# Sheet4.net
KiCad netlist of a schematic drawn in Altium Designer
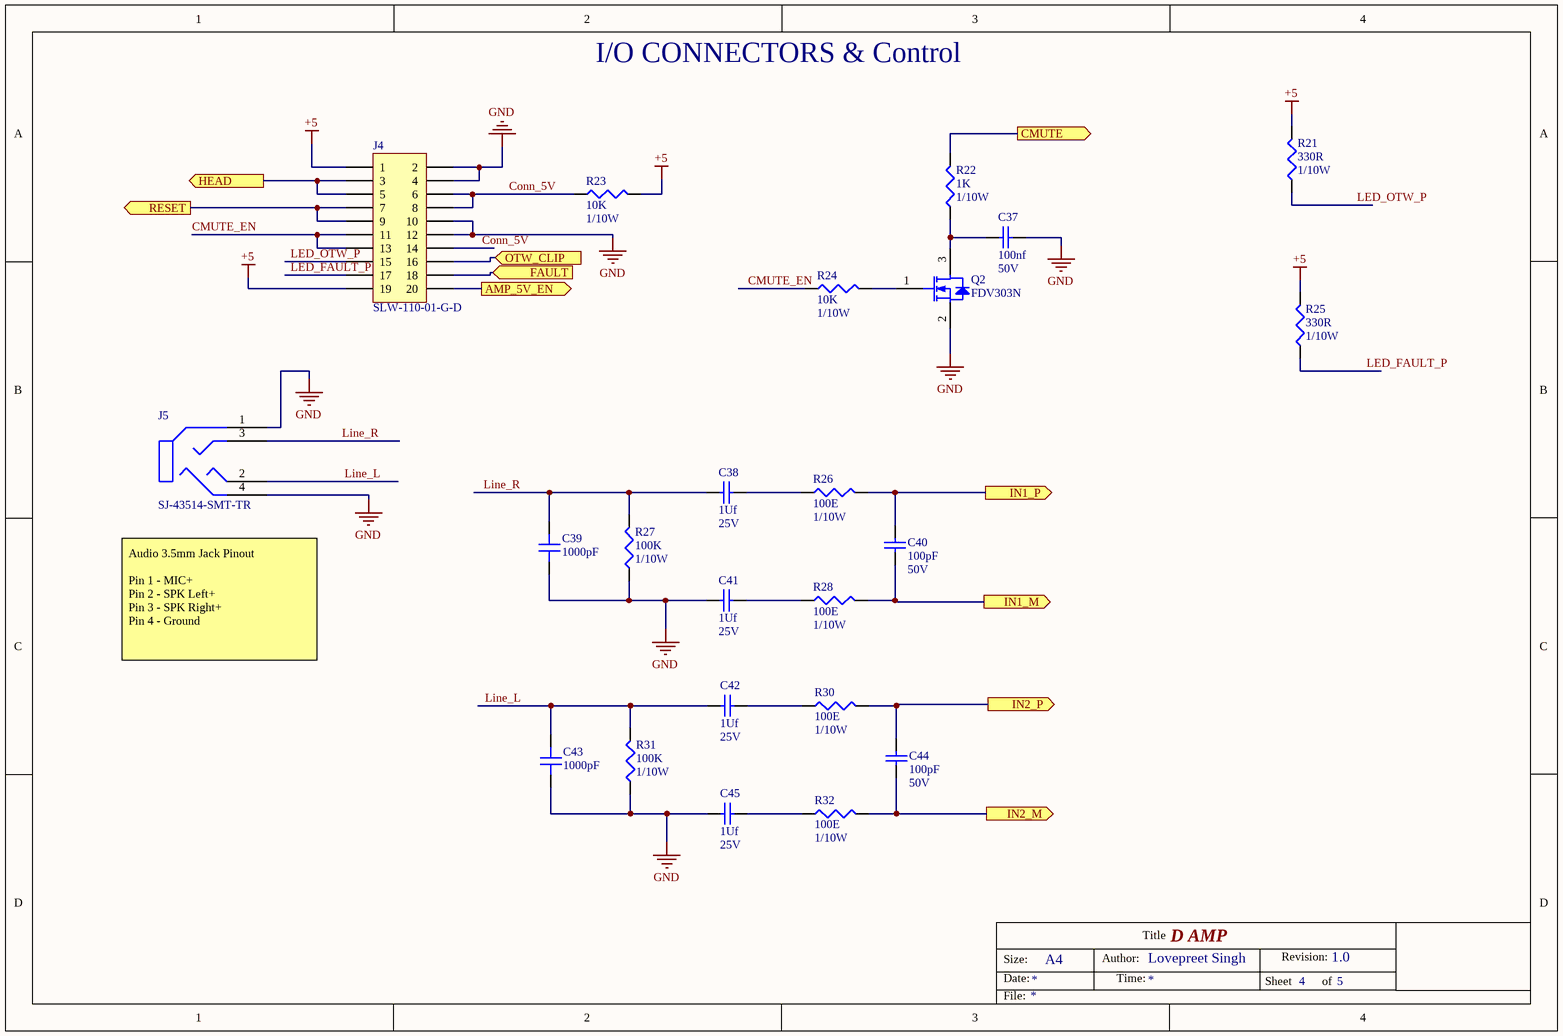
[diagram p0: Sheet4.SchDoc]

(export (version "E")
  (design (tool "Eeschema 10.0.6"))
  (components
    (comp (ref "C37")
      (value "100nf")
      (footprint "C0603")
      (description "CAP CER 100NF 10% 50V X7R 0603")
      (fields (field (name "VRATING") "50V"))
      (libsource (lib "Database_Libs1") (part "CAP_NPOL"))
    )
    (comp (ref "C38")
      (value "1Uf")
      (footprint "C0603")
      (description "CAP MLCC SMD 25V 1uF 10% X7R 0603")
      (fields (field (name "VRATING") "25V"))
      (libsource (lib "Database_Libs1") (part "CAP_NPOL"))
    )
    (comp (ref "C39")
      (value "1000pF")
      (footprint "CAP 0603_1608")
      (description "CAP CER 0603 1NF 16V X7R 10%")
      (fields (field (name "PART NUMBER") "C0603C102K4RECAUTO") (field (name "MANUFACTURER") "KEMET"))
      (libsource (lib "Celestial Altium Library - altium_library") (part "Capacitor"))
    )
    (comp (ref "C40")
      (value "100pF")
      (footprint "C0603")
      (description "CAP 100PF 5% 50V 0603")
      (fields (field (name "VRATING") "50V"))
      (libsource (lib "Database_Libs1") (part "CAP_NPOL"))
    )
    (comp (ref "C41")
      (value "1Uf")
      (footprint "C0603")
      (description "CAP MLCC SMD 25V 1uF 10% X7R 0603")
      (fields (field (name "VRATING") "25V"))
      (libsource (lib "Database_Libs1") (part "CAP_NPOL"))
    )
    (comp (ref "C42")
      (value "1Uf")
      (footprint "C0603")
      (description "CAP MLCC SMD 25V 1uF 10% X7R 0603")
      (fields (field (name "VRATING") "25V"))
      (libsource (lib "Database_Libs1") (part "CAP_NPOL"))
    )
    (comp (ref "C43")
      (value "1000pF")
      (footprint "CAP 0603_1608")
      (description "CAP CER 0603 1NF 16V X7R 10%")
      (fields (field (name "PART NUMBER") "C0603C102K4RECAUTO") (field (name "MANUFACTURER") "KEMET"))
      (libsource (lib "Celestial Altium Library - altium_library") (part "Capacitor"))
    )
    (comp (ref "C44")
      (value "100pF")
      (footprint "C0603")
      (description "CAP 100PF 5% 50V 0603")
      (fields (field (name "VRATING") "50V"))
      (libsource (lib "Database_Libs1") (part "CAP_NPOL"))
    )
    (comp (ref "C45")
      (value "1Uf")
      (footprint "C0603")
      (description "CAP MLCC SMD 25V 1uF 10% X7R 0603")
      (fields (field (name "VRATING") "25V"))
      (libsource (lib "Database_Libs1") (part "CAP_NPOL"))
    )
    (comp (ref "J4")
      (value "SLW-110-01-G-D")
      (footprint "HDR2X10")
      (description "CONN HSG 20PIN 2.54MM STR DUALROW")
      (libsource (lib "Database_Libs1") (part "Header 10X2"))
    )
    (comp (ref "J5")
      (value "SJ-43514-SMT-TR")
      (footprint "CUI SJ-43514-SMT-TR")
      (description "CONN JACK 4COND 3.5MM SMD R/A")
      (fields (field (name "MANUFACTURER") "CUI Devices"))
      (libsource (lib "Celestial Altium Library - altium_library") (part "CUI SJ-43514"))
    )
    (comp (ref "Q2")
      (value "FDV303N")
      (footprint "SOT23_123")
      (description "TRANS N-CH MOSFET 25V 0.68A SOT23")
      (libsource (lib "Database_Libs1") (part "FDV303N"))
    )
    (comp (ref "R21")
      (value "330R")
      (footprint "R0603")
      (description "RES  SMD 330R 5% 1/10W 0603")
      (fields (field (name "PRATING") "1/10W"))
      (libsource (lib "Database_Libs1") (part "RES"))
    )
    (comp (ref "R22")
      (value "1K")
      (footprint "R0603")
      (description "RES SMD 1K 1% 1/10W 0603")
      (fields (field (name "PRATING") "1/10W"))
      (libsource (lib "Database_Libs1") (part "RES"))
    )
    (comp (ref "R23")
      (value "10K")
      (footprint "R0603")
      (description "RES SMD 10K 1% 1/10W 0603")
      (fields (field (name "PRATING") "1/10W"))
      (libsource (lib "Database_Libs1") (part "RES"))
    )
    (comp (ref "R24")
      (value "10K")
      (footprint "R0603")
      (description "RES SMD 10K 1% 1/10W 0603")
      (fields (field (name "PRATING") "1/10W"))
      (libsource (lib "Database_Libs1") (part "RES"))
    )
    (comp (ref "R25")
      (value "330R")
      (footprint "R0603")
      (description "RES  SMD 330R 5% 1/10W 0603")
      (fields (field (name "PRATING") "1/10W"))
      (libsource (lib "Database_Libs1") (part "RES"))
    )
    (comp (ref "R26")
      (value "100E")
      (footprint "R0603")
      (description "RES SMD 100E 1% 1/10W 0603")
      (fields (field (name "PRATING") "1/10W"))
      (libsource (lib "Database_Libs1") (part "RES"))
    )
    (comp (ref "R27")
      (value "100K")
      (footprint "R0603")
      (description "RES SMD 100K 1% 1/10W 0603")
      (fields (field (name "PRATING") "1/10W"))
      (libsource (lib "Database_Libs1") (part "RES"))
    )
    (comp (ref "R28")
      (value "100E")
      (footprint "R0603")
      (description "RES SMD 100E 1% 1/10W 0603")
      (fields (field (name "PRATING") "1/10W"))
      (libsource (lib "Database_Libs1") (part "RES"))
    )
    (comp (ref "R30")
      (value "100E")
      (footprint "R0603")
      (description "RES SMD 100E 1% 1/10W 0603")
      (fields (field (name "PRATING") "1/10W"))
      (libsource (lib "Database_Libs1") (part "RES"))
    )
    (comp (ref "R31")
      (value "100K")
      (footprint "R0603")
      (description "RES SMD 100K 1% 1/10W 0603")
      (fields (field (name "PRATING") "1/10W"))
      (libsource (lib "Database_Libs1") (part "RES"))
    )
    (comp (ref "R32")
      (value "100E")
      (footprint "R0603")
      (description "RES SMD 100E 1% 1/10W 0603")
      (fields (field (name "PRATING") "1/10W"))
      (libsource (lib "Database_Libs1") (part "RES"))
    )
  )
  (nets
    (net (code "1") (name "+5") (class "Default")
      (node (ref "J4") (pin "1") (pinfunction "1_1") (pintype "passive"))
      (node (ref "J4") (pin "19") (pinfunction "19_19") (pintype "passive"))
      (node (ref "R21") (pin "2") (pinfunction "2_2") (pintype "passive"))
      (node (ref "R23") (pin "2") (pinfunction "2_2") (pintype "passive"))
      (node (ref "R25") (pin "2") (pinfunction "2_2") (pintype "passive"))
    )
    (net (code "2") (name "/AMP_5V_EN") (class "Default")
      (node (ref "J4") (pin "20") (pinfunction "20_20") (pintype "passive"))
    )
    (net (code "3") (name "/CMUTE") (class "Default")
      (node (ref "R22") (pin "2") (pinfunction "2_2") (pintype "passive"))
    )
    (net (code "4") (name "/CMUTE_EN") (class "Default")
      (node (ref "J4") (pin "11") (pinfunction "11_11") (pintype "passive"))
      (node (ref "J4") (pin "13") (pinfunction "13_13") (pintype "passive"))
      (node (ref "R24") (pin "1") (pinfunction "1_1") (pintype "passive"))
    )
    (net (code "5") (name "/Conn_5V") (class "Default")
      (node (ref "J4") (pin "14") (pinfunction "14_14") (pintype "passive"))
      (node (ref "J4") (pin "6") (pinfunction "6_6") (pintype "passive"))
      (node (ref "J4") (pin "8") (pinfunction "8_8") (pintype "passive"))
      (node (ref "R23") (pin "1") (pinfunction "1_1") (pintype "passive"))
    )
    (net (code "6") (name "/FAULT") (class "Default")
      (node (ref "J4") (pin "18") (pinfunction "18_18") (pintype "passive"))
    )
    (net (code "7") (name "/HEAD") (class "Default")
      (node (ref "J4") (pin "3") (pinfunction "3_3") (pintype "passive"))
      (node (ref "J4") (pin "5") (pinfunction "5_5") (pintype "passive"))
    )
    (net (code "8") (name "/IN1_M") (class "Default")
      (node (ref "C40") (pin "1") (pinfunction "1_1") (pintype "passive"))
      (node (ref "R28") (pin "2") (pinfunction "2_2") (pintype "passive"))
    )
    (net (code "9") (name "/IN1_P") (class "Default")
      (node (ref "C40") (pin "2") (pinfunction "2_2") (pintype "passive"))
      (node (ref "R26") (pin "2") (pinfunction "2_2") (pintype "passive"))
    )
    (net (code "10") (name "/IN2_M") (class "Default")
      (node (ref "C44") (pin "1") (pinfunction "1_1") (pintype "passive"))
      (node (ref "R32") (pin "2") (pinfunction "2_2") (pintype "passive"))
    )
    (net (code "11") (name "/IN2_P") (class "Default")
      (node (ref "C44") (pin "2") (pinfunction "2_2") (pintype "passive"))
      (node (ref "R30") (pin "2") (pinfunction "2_2") (pintype "passive"))
    )
    (net (code "12") (name "/LED_FAULT_P") (class "Default")
      (node (ref "J4") (pin "17") (pinfunction "17_17") (pintype "passive"))
      (node (ref "R25") (pin "1") (pinfunction "1_1") (pintype "passive"))
    )
    (net (code "13") (name "/LED_OTW_P") (class "Default")
      (node (ref "J4") (pin "15") (pinfunction "15_15") (pintype "passive"))
      (node (ref "R21") (pin "1") (pinfunction "1_1") (pintype "passive"))
    )
    (net (code "14") (name "/Line_L") (class "Default")
      (node (ref "C42") (pin "1") (pinfunction "1_1") (pintype "passive"))
      (node (ref "C43") (pin "2") (pinfunction "2_2") (pintype "passive"))
      (node (ref "J5") (pin "2") (pinfunction "TIP_2") (pintype "passive"))
      (node (ref "R31") (pin "2") (pinfunction "2_2") (pintype "passive"))
    )
    (net (code "15") (name "/Line_R") (class "Default")
      (node (ref "C38") (pin "1") (pinfunction "1_1") (pintype "passive"))
      (node (ref "C39") (pin "2") (pinfunction "2_2") (pintype "passive"))
      (node (ref "J5") (pin "3") (pinfunction "RING_1_3") (pintype "passive"))
      (node (ref "R27") (pin "2") (pinfunction "2_2") (pintype "passive"))
    )
    (net (code "16") (name "/OTW_CLIP") (class "Default")
      (node (ref "J4") (pin "16") (pinfunction "16_16") (pintype "passive"))
    )
    (net (code "17") (name "/RESET") (class "Default")
      (node (ref "J4") (pin "7") (pinfunction "7_7") (pintype "passive"))
      (node (ref "J4") (pin "9") (pinfunction "9_9") (pintype "passive"))
    )
    (net (code "18") (name "GND") (class "Default")
      (node (ref "C37") (pin "2") (pinfunction "2_2") (pintype "passive"))
      (node (ref "C39") (pin "1") (pinfunction "1_1") (pintype "passive"))
      (node (ref "C41") (pin "1") (pinfunction "1_1") (pintype "passive"))
      (node (ref "C43") (pin "1") (pinfunction "1_1") (pintype "passive"))
      (node (ref "C45") (pin "1") (pinfunction "1_1") (pintype "passive"))
      (node (ref "J4") (pin "10") (pinfunction "10_10") (pintype "passive"))
      (node (ref "J4") (pin "12") (pinfunction "12_12") (pintype "passive"))
      (node (ref "J4") (pin "2") (pinfunction "2_2") (pintype "passive"))
      (node (ref "J4") (pin "4") (pinfunction "4_4") (pintype "passive"))
      (node (ref "J5") (pin "1") (pinfunction "SLEEVE_1") (pintype "passive"))
      (node (ref "J5") (pin "4") (pinfunction "RING_2_4") (pintype "passive"))
      (node (ref "Q2") (pin "2") (pinfunction "S_2") (pintype "passive"))
      (node (ref "R27") (pin "1") (pinfunction "1_1") (pintype "passive"))
      (node (ref "R31") (pin "1") (pinfunction "1_1") (pintype "passive"))
    )
    (net (code "19") (name "Net-(C38-Pad2)") (class "Default")
      (node (ref "C38") (pin "2") (pinfunction "2_2") (pintype "passive"))
      (node (ref "R26") (pin "1") (pinfunction "1_1") (pintype "passive"))
    )
    (net (code "20") (name "Net-(C41-Pad2)") (class "Default")
      (node (ref "C41") (pin "2") (pinfunction "2_2") (pintype "passive"))
      (node (ref "R28") (pin "1") (pinfunction "1_1") (pintype "passive"))
    )
    (net (code "21") (name "Net-(C42-Pad2)") (class "Default")
      (node (ref "C42") (pin "2") (pinfunction "2_2") (pintype "passive"))
      (node (ref "R30") (pin "1") (pinfunction "1_1") (pintype "passive"))
    )
    (net (code "22") (name "Net-(C45-Pad2)") (class "Default")
      (node (ref "C45") (pin "2") (pinfunction "2_2") (pintype "passive"))
      (node (ref "R32") (pin "1") (pinfunction "1_1") (pintype "passive"))
    )
    (net (code "23") (name "Net-(Q2-D)") (class "Default")
      (node (ref "C37") (pin "1") (pinfunction "1_1") (pintype "passive"))
      (node (ref "Q2") (pin "3") (pinfunction "D_3") (pintype "passive"))
      (node (ref "R22") (pin "1") (pinfunction "1_1") (pintype "passive"))
    )
    (net (code "24") (name "Net-(Q2-G)") (class "Default")
      (node (ref "Q2") (pin "1") (pinfunction "G_1") (pintype "passive"))
      (node (ref "R24") (pin "2") (pinfunction "2_2") (pintype "passive"))
    )
  )
)
